# main-single-esp32.net
KiCad netlist of a schematic drawn in EAGLE
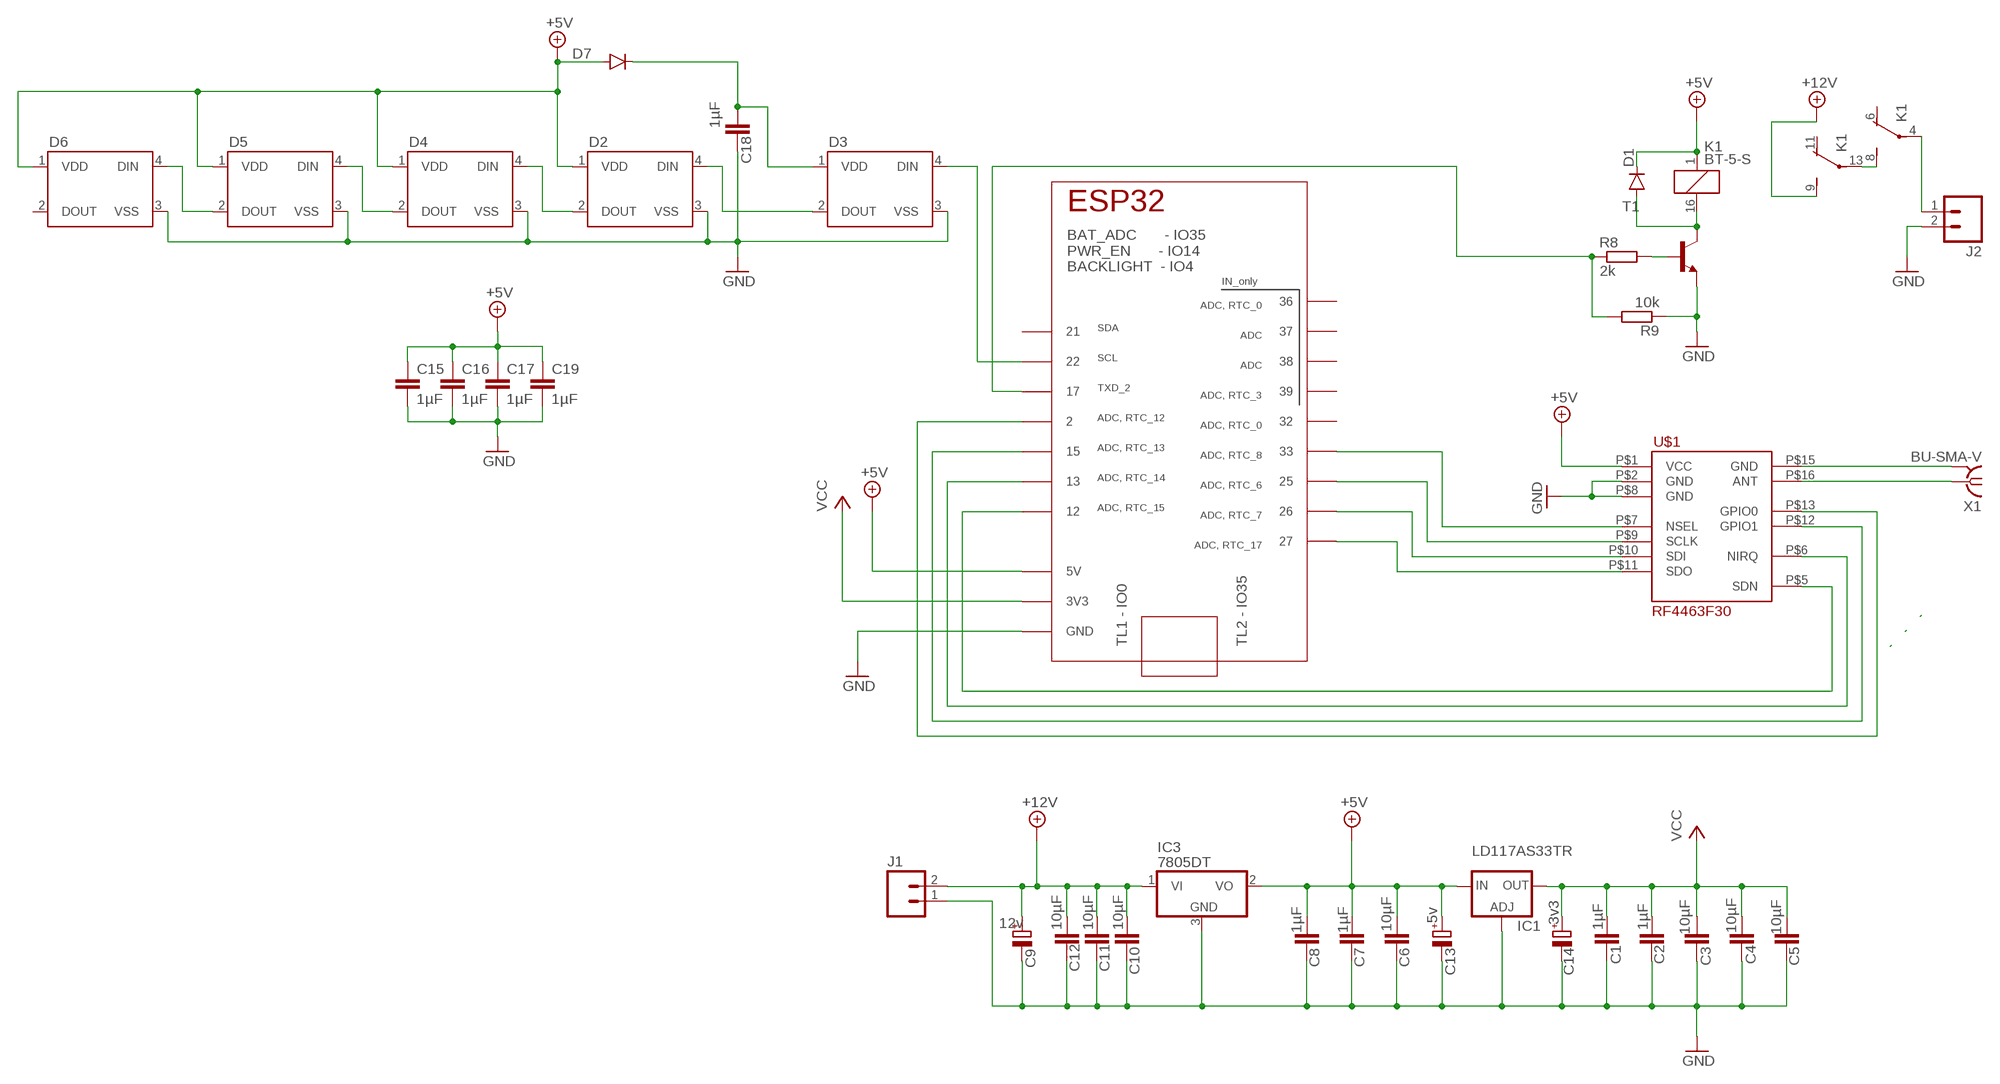
[diagram p0: schematic, sheet 1]

(export (version "E")
  (design (tool "Eeschema 10.0.6"))
  (components
    (comp (ref "C1")
      (value "1µF")
      (footprint "eagle-import:C1206K")
      (libsource (lib "eagle-import") (part "C-EUC1206K"))
    )
    (comp (ref "C2")
      (value "1µF")
      (footprint "eagle-import:C1206K")
      (libsource (lib "eagle-import") (part "C-EUC1206K"))
    )
    (comp (ref "C3")
      (value "10µF")
      (footprint "eagle-import:C1206K")
      (libsource (lib "eagle-import") (part "C-EUC1206K"))
    )
    (comp (ref "C4")
      (value "10µF")
      (footprint "eagle-import:C1206K")
      (libsource (lib "eagle-import") (part "C-EUC1206K"))
    )
    (comp (ref "C5")
      (value "10µF")
      (footprint "eagle-import:C1206K")
      (libsource (lib "eagle-import") (part "C-EUC1206K"))
    )
    (comp (ref "C6")
      (value "10µF")
      (footprint "eagle-import:C1206K")
      (libsource (lib "eagle-import") (part "C-EUC1206K"))
    )
    (comp (ref "C7")
      (value "1µF")
      (footprint "eagle-import:C1206K")
      (libsource (lib "eagle-import") (part "C-EUC1206K"))
    )
    (comp (ref "C8")
      (value "1µF")
      (footprint "eagle-import:C1206K")
      (libsource (lib "eagle-import") (part "C-EUC1206K"))
    )
    (comp (ref "C9")
      (value "12v")
      (footprint "eagle-import:D_7343-31W")
      (libsource (lib "eagle-import") (part "CPOL-EUD/7343-31W"))
    )
    (comp (ref "C10")
      (value "10µF")
      (footprint "eagle-import:C1206K")
      (libsource (lib "eagle-import") (part "C-EUC1206K"))
    )
    (comp (ref "C11")
      (value "10µF")
      (footprint "eagle-import:C1206K")
      (libsource (lib "eagle-import") (part "C-EUC1206K"))
    )
    (comp (ref "C12")
      (value "10µF")
      (footprint "eagle-import:C1206K")
      (libsource (lib "eagle-import") (part "C-EUC1206K"))
    )
    (comp (ref "C13")
      (value "5v")
      (footprint "eagle-import:D_7343-31W")
      (libsource (lib "eagle-import") (part "CPOL-EUD/7343-31W"))
    )
    (comp (ref "C14")
      (value "3v3")
      (footprint "eagle-import:D_7343-31W")
      (libsource (lib "eagle-import") (part "CPOL-EUD/7343-31W"))
    )
    (comp (ref "C15")
      (value "1µF")
      (footprint "eagle-import:C0805")
      (libsource (lib "eagle-import") (part "C-EUC0805"))
    )
    (comp (ref "C16")
      (value "1µF")
      (footprint "eagle-import:C0805")
      (libsource (lib "eagle-import") (part "C-EUC0805"))
    )
    (comp (ref "C17")
      (value "1µF")
      (footprint "eagle-import:C0805")
      (libsource (lib "eagle-import") (part "C-EUC0805"))
    )
    (comp (ref "C18")
      (value "1µF")
      (footprint "eagle-import:C0805")
      (libsource (lib "eagle-import") (part "C-EUC0805"))
    )
    (comp (ref "C19")
      (value "1µF")
      (footprint "eagle-import:C0805")
      (libsource (lib "eagle-import") (part "C-EUC0805"))
    )
    (comp (ref "D1")
      (value "DIODESMA")
      (footprint "eagle-import:SMA-DIODE")
      (libsource (lib "eagle-import") (part "DIODESMA"))
    )
    (comp (ref "D2")
      (value "WS2812B")
      (footprint "eagle-import:WS2812B")
      (libsource (lib "eagle-import") (part "WS2812B"))
    )
    (comp (ref "D3")
      (value "WS2812B")
      (footprint "eagle-import:WS2812B")
      (libsource (lib "eagle-import") (part "WS2812B"))
    )
    (comp (ref "D4")
      (value "WS2812B")
      (footprint "eagle-import:WS2812B")
      (libsource (lib "eagle-import") (part "WS2812B"))
    )
    (comp (ref "D5")
      (value "WS2812B")
      (footprint "eagle-import:WS2812B")
      (libsource (lib "eagle-import") (part "WS2812B"))
    )
    (comp (ref "D6")
      (value "WS2812B")
      (footprint "eagle-import:WS2812B")
      (libsource (lib "eagle-import") (part "WS2812B"))
    )
    (comp (ref "D7")
      (value "DIODESMA")
      (footprint "eagle-import:SMA-DIODE")
      (libsource (lib "eagle-import") (part "DIODESMA"))
    )
    (comp (ref "IC1")
      (value "LD117AS33TR")
      (footprint "eagle-import:SOT223")
      (libsource (lib "eagle-import") (part "LD117A?S33TR"))
    )
    (comp (ref "IC2")
      (value "TTGO_DISP")
      (footprint "eagle-import:TTGO_DISP_DEFAULT")
      (libsource (lib "eagle-import") (part "TTGO_DISP"))
    )
    (comp (ref "IC3")
      (value "7805DT")
      (footprint "eagle-import:TO252")
      (libsource (lib "eagle-import") (part "78DT05"))
    )
    (comp (ref "J1")
      (value "M023.5MM-NO_SILK")
      (footprint "eagle-import:SCREWTERMINAL-3.5MM-2-NS")
      (libsource (lib "eagle-import") (part "M023.5MM-NO_SILK"))
    )
    (comp (ref "J2")
      (value "M023.5MM-NO_SILK")
      (footprint "eagle-import:SCREWTERMINAL-3.5MM-2-NS")
      (libsource (lib "eagle-import") (part "M023.5MM-NO_SILK"))
    )
    (comp (ref "K1")
      (value "BT-5-S")
      (footprint "eagle-import:BT-XX-S")
      (libsource (lib "eagle-import") (part "BT--S5"))
    )
    (comp (ref "R8")
      (value "2k")
      (footprint "eagle-import:R1206")
      (libsource (lib "eagle-import") (part "R-EU_R1206"))
    )
    (comp (ref "R9")
      (value "10k")
      (footprint "eagle-import:R1206")
      (libsource (lib "eagle-import") (part "R-EU_R1206"))
    )
    (comp (ref "T1")
      (value "MMBT2222ALT1-NPN-SOT23-BEC")
      (footprint "eagle-import:SOT23-BEC")
      (libsource (lib "eagle-import") (part "-NPN-SOT23-BECMMBT2222ALT1"))
    )
    (comp (ref "U$1")
      (value "RF4463F30")
      (footprint "eagle-import:NICERF_16PIN_SPI_TRANSCEIVER")
      (libsource (lib "eagle-import") (part "RF4463F30"))
    )
    (comp (ref "X1")
      (value "BU-SMA-V")
      (footprint "eagle-import:BU-SMA-V")
      (libsource (lib "eagle-import") (part "BU-SMA-V"))
    )
  )
  (nets
    (net (code "1") (name "+5V") (class "Default")
      (node (ref "C13") (pin "+") (pinfunction "+_+") (pintype "passive"))
      (node (ref "C15") (pin "1") (pinfunction "1_1") (pintype "passive"))
      (node (ref "C16") (pin "1") (pinfunction "1_1") (pintype "passive"))
      (node (ref "C17") (pin "1") (pinfunction "1_1") (pintype "passive"))
      (node (ref "C19") (pin "1") (pinfunction "1_1") (pintype "passive"))
      (node (ref "C6") (pin "1") (pinfunction "1_1") (pintype "passive"))
      (node (ref "C7") (pin "1") (pinfunction "1_1") (pintype "passive"))
      (node (ref "C8") (pin "1") (pinfunction "1_1") (pintype "passive"))
      (node (ref "D1") (pin "C") (pinfunction "C_C") (pintype "passive"))
      (node (ref "D2") (pin "1") (pinfunction "VDD_1") (pintype "power_in"))
      (node (ref "D4") (pin "1") (pinfunction "VDD_1") (pintype "power_in"))
      (node (ref "D5") (pin "1") (pinfunction "VDD_1") (pintype "power_in"))
      (node (ref "D6") (pin "1") (pinfunction "VDD_1") (pintype "power_in"))
      (node (ref "D7") (pin "A") (pinfunction "A_A") (pintype "passive"))
      (node (ref "IC1") (pin "3") (pinfunction "IN_3") (pintype "input"))
      (node (ref "IC2") (pin "5V") (pinfunction "5V_5V") (pintype "bidirectional"))
      (node (ref "IC3") (pin "2") (pinfunction "VO_2") (pintype "passive"))
      (node (ref "K1") (pin "1") (pinfunction "1_1") (pintype "passive"))
      (node (ref "U$1") (pin "P$1") (pinfunction "VCC_P$1") (pintype "bidirectional"))
    )
    (net (code "2") (name "+12V") (class "Default")
      (node (ref "C10") (pin "1") (pinfunction "1_1") (pintype "passive"))
      (node (ref "C11") (pin "1") (pinfunction "1_1") (pintype "passive"))
      (node (ref "C12") (pin "1") (pinfunction "1_1") (pintype "passive"))
      (node (ref "C9") (pin "+") (pinfunction "+_+") (pintype "passive"))
      (node (ref "IC3") (pin "1") (pinfunction "VI_1") (pintype "input"))
      (node (ref "J1") (pin "2") (pinfunction "2_2") (pintype "passive"))
      (node (ref "K1") (pin "9") (pinfunction "S_9") (pintype "passive"))
    )
    (net (code "3") (name "GND") (class "Default")
      (node (ref "C1") (pin "2") (pinfunction "2_2") (pintype "passive"))
      (node (ref "C10") (pin "2") (pinfunction "2_2") (pintype "passive"))
      (node (ref "C11") (pin "2") (pinfunction "2_2") (pintype "passive"))
      (node (ref "C12") (pin "2") (pinfunction "2_2") (pintype "passive"))
      (node (ref "C13") (pin "-") (pinfunction "-_-") (pintype "passive"))
      (node (ref "C14") (pin "-") (pinfunction "-_-") (pintype "passive"))
      (node (ref "C15") (pin "2") (pinfunction "2_2") (pintype "passive"))
      (node (ref "C16") (pin "2") (pinfunction "2_2") (pintype "passive"))
      (node (ref "C17") (pin "2") (pinfunction "2_2") (pintype "passive"))
      (node (ref "C18") (pin "2") (pinfunction "2_2") (pintype "passive"))
      (node (ref "C19") (pin "2") (pinfunction "2_2") (pintype "passive"))
      (node (ref "C2") (pin "2") (pinfunction "2_2") (pintype "passive"))
      (node (ref "C3") (pin "2") (pinfunction "2_2") (pintype "passive"))
      (node (ref "C4") (pin "2") (pinfunction "2_2") (pintype "passive"))
      (node (ref "C5") (pin "2") (pinfunction "2_2") (pintype "passive"))
      (node (ref "C6") (pin "2") (pinfunction "2_2") (pintype "passive"))
      (node (ref "C7") (pin "2") (pinfunction "2_2") (pintype "passive"))
      (node (ref "C8") (pin "2") (pinfunction "2_2") (pintype "passive"))
      (node (ref "C9") (pin "-") (pinfunction "-_-") (pintype "passive"))
      (node (ref "D2") (pin "3") (pinfunction "VSS_3") (pintype "power_in"))
      (node (ref "D3") (pin "3") (pinfunction "VSS_3") (pintype "power_in"))
      (node (ref "D4") (pin "3") (pinfunction "VSS_3") (pintype "power_in"))
      (node (ref "D5") (pin "3") (pinfunction "VSS_3") (pintype "power_in"))
      (node (ref "D6") (pin "3") (pinfunction "VSS_3") (pintype "power_in"))
      (node (ref "IC1") (pin "1") (pinfunction "ADJ_1") (pintype "input"))
      (node (ref "IC2") (pin "GND_1") (pinfunction "GND_GND_1") (pintype "bidirectional"))
      (node (ref "IC2") (pin "GND_2") (pinfunction "GND_GND_2") (pintype "bidirectional"))
      (node (ref "IC2") (pin "GND_3") (pinfunction "GND_GND_3") (pintype "bidirectional"))
      (node (ref "IC2") (pin "GND_4") (pinfunction "GND_GND_4") (pintype "bidirectional"))
      (node (ref "IC2") (pin "GND_5") (pinfunction "GND_GND_5") (pintype "bidirectional"))
      (node (ref "IC3") (pin "3") (pinfunction "GND_3") (pintype "passive"))
      (node (ref "J1") (pin "1") (pinfunction "1_1") (pintype "passive"))
      (node (ref "J2") (pin "2") (pinfunction "2_2") (pintype "passive"))
      (node (ref "R9") (pin "1") (pinfunction "1_1") (pintype "passive"))
      (node (ref "T1") (pin "E") (pinfunction "E_E") (pintype "passive"))
      (node (ref "U$1") (pin "P$2") (pinfunction "GND_P$2") (pintype "bidirectional"))
      (node (ref "U$1") (pin "P$8") (pinfunction "GND_P$8") (pintype "bidirectional"))
    )
    (net (code "4") (name "Net-(D2-DIN)") (class "Default")
      (node (ref "D2") (pin "4") (pinfunction "DIN_4") (pintype "input"))
      (node (ref "D3") (pin "2") (pinfunction "DOUT_2") (pintype "output"))
    )
    (net (code "5") (name "Net-(D2-DOUT)") (class "Default")
      (node (ref "D2") (pin "2") (pinfunction "DOUT_2") (pintype "output"))
      (node (ref "D4") (pin "4") (pinfunction "DIN_4") (pintype "input"))
    )
    (net (code "6") (name "Net-(D3-DIN)") (class "Default")
      (node (ref "D3") (pin "4") (pinfunction "DIN_4") (pintype "input"))
      (node (ref "IC2") (pin "22") (pinfunction "22_22") (pintype "bidirectional"))
    )
    (net (code "7") (name "Net-(D3-VDD)") (class "Default")
      (node (ref "C18") (pin "1") (pinfunction "1_1") (pintype "passive"))
      (node (ref "D3") (pin "1") (pinfunction "VDD_1") (pintype "power_in"))
      (node (ref "D7") (pin "C") (pinfunction "C_C") (pintype "passive"))
    )
    (net (code "8") (name "Net-(D4-DOUT)") (class "Default")
      (node (ref "D4") (pin "2") (pinfunction "DOUT_2") (pintype "output"))
      (node (ref "D5") (pin "4") (pinfunction "DIN_4") (pintype "input"))
    )
    (net (code "9") (name "Net-(D5-DOUT)") (class "Default")
      (node (ref "D5") (pin "2") (pinfunction "DOUT_2") (pintype "output"))
      (node (ref "D6") (pin "4") (pinfunction "DIN_4") (pintype "input"))
    )
    (net (code "10") (name "Net-(IC2-Pad17)") (class "Default")
      (node (ref "IC2") (pin "17") (pinfunction "17_17") (pintype "bidirectional"))
      (node (ref "R8") (pin "1") (pinfunction "1_1") (pintype "passive"))
      (node (ref "R9") (pin "2") (pinfunction "2_2") (pintype "passive"))
    )
    (net (code "11") (name "Net-(K1A-P)") (class "Default")
      (node (ref "J2") (pin "1") (pinfunction "1_1") (pintype "passive"))
      (node (ref "K1") (pin "4") (pinfunction "P_4") (pintype "passive"))
    )
    (net (code "12") (name "Net-(K1A-S)") (class "Default")
      (node (ref "K1") (pin "13") (pinfunction "P_13") (pintype "passive"))
      (node (ref "K1") (pin "8") (pinfunction "S_8") (pintype "passive"))
    )
    (net (code "13") (name "Net-(K1C-2)") (class "Default")
      (node (ref "D1") (pin "A") (pinfunction "A_A") (pintype "passive"))
      (node (ref "K1") (pin "16") (pinfunction "2_16") (pintype "passive"))
      (node (ref "T1") (pin "C") (pinfunction "C_C") (pintype "passive"))
    )
    (net (code "14") (name "Net-(R8-Pad2)") (class "Default")
      (node (ref "R8") (pin "2") (pinfunction "2_2") (pintype "passive"))
      (node (ref "T1") (pin "B") (pinfunction "B_B") (pintype "passive"))
    )
    (net (code "15") (name "Net-(U$1-ANT)") (class "Default")
      (node (ref "U$1") (pin "P$16") (pinfunction "ANT_P$16") (pintype "bidirectional"))
      (node (ref "X1") (pin "1") (pinfunction "1_1") (pintype "passive"))
    )
    (net (code "16") (name "Net-(U$1-GND-PadP$15)") (class "Default")
      (node (ref "U$1") (pin "P$15") (pinfunction "GND_P$15") (pintype "bidirectional"))
      (node (ref "X1") (pin "2") (pinfunction "2_2") (pintype "passive"))
      (node (ref "X1") (pin "3") (pinfunction "2_3") (pintype "passive"))
      (node (ref "X1") (pin "4") (pinfunction "2_4") (pintype "passive"))
      (node (ref "X1") (pin "5") (pinfunction "2_5") (pintype "passive"))
    )
    (net (code "17") (name "Net-(U$1-GPIO0)") (class "Default")
      (node (ref "IC2") (pin "2") (pinfunction "2_2") (pintype "bidirectional"))
      (node (ref "U$1") (pin "P$13") (pinfunction "GPIO0_P$13") (pintype "bidirectional"))
    )
    (net (code "18") (name "Net-(U$1-GPIO1)") (class "Default")
      (node (ref "IC2") (pin "15") (pinfunction "15_15") (pintype "bidirectional"))
      (node (ref "U$1") (pin "P$12") (pinfunction "GPIO1_P$12") (pintype "bidirectional"))
    )
    (net (code "19") (name "Net-(U$1-NIRQ)") (class "Default")
      (node (ref "IC2") (pin "13") (pinfunction "13_13") (pintype "bidirectional"))
      (node (ref "U$1") (pin "P$6") (pinfunction "NIRQ_P$6") (pintype "bidirectional"))
    )
    (net (code "20") (name "Net-(U$1-NSEL)") (class "Default")
      (node (ref "IC2") (pin "33") (pinfunction "33_33") (pintype "bidirectional"))
      (node (ref "U$1") (pin "P$7") (pinfunction "NSEL_P$7") (pintype "bidirectional"))
    )
    (net (code "21") (name "Net-(U$1-SCLK)") (class "Default")
      (node (ref "IC2") (pin "25") (pinfunction "25_25") (pintype "bidirectional"))
      (node (ref "U$1") (pin "P$9") (pinfunction "SCLK_P$9") (pintype "bidirectional"))
    )
    (net (code "22") (name "Net-(U$1-SDI)") (class "Default")
      (node (ref "IC2") (pin "26") (pinfunction "26_26") (pintype "bidirectional"))
      (node (ref "U$1") (pin "P$10") (pinfunction "SDI_P$10") (pintype "bidirectional"))
    )
    (net (code "23") (name "Net-(U$1-SDN)") (class "Default")
      (node (ref "IC2") (pin "12") (pinfunction "12_12") (pintype "bidirectional"))
      (node (ref "U$1") (pin "P$5") (pinfunction "SDN_P$5") (pintype "bidirectional"))
    )
    (net (code "24") (name "Net-(U$1-SDO)") (class "Default")
      (node (ref "IC2") (pin "27") (pinfunction "27_27") (pintype "bidirectional"))
      (node (ref "U$1") (pin "P$11") (pinfunction "SDO_P$11") (pintype "bidirectional"))
    )
    (net (code "25") (name "VCC") (class "Default")
      (node (ref "C1") (pin "1") (pinfunction "1_1") (pintype "passive"))
      (node (ref "C14") (pin "+") (pinfunction "+_+") (pintype "passive"))
      (node (ref "C2") (pin "1") (pinfunction "1_1") (pintype "passive"))
      (node (ref "C3") (pin "1") (pinfunction "1_1") (pintype "passive"))
      (node (ref "C4") (pin "1") (pinfunction "1_1") (pintype "passive"))
      (node (ref "C5") (pin "1") (pinfunction "1_1") (pintype "passive"))
      (node (ref "IC1") (pin "4") (pinfunction "OUT_4") (pintype "passive"))
      (node (ref "IC2") (pin "3V3_1") (pinfunction "3V3_3V3_1") (pintype "bidirectional"))
      (node (ref "IC2") (pin "3V3_2") (pinfunction "3V3_3V3_2") (pintype "bidirectional"))
    )
    (net (code "26") (name "unconnected-(D6-DOUT-Pad2)") (class "Default")
      (node (ref "D6") (pin "2") (pinfunction "DOUT_2") (pintype "output"))
    )
    (net (code "27") (name "unconnected-(IC2-Pad21)") (class "Default")
      (node (ref "IC2") (pin "21") (pinfunction "21_21") (pintype "bidirectional"))
    )
    (net (code "28") (name "unconnected-(IC2-Pad32)") (class "Default")
      (node (ref "IC2") (pin "32") (pinfunction "32_32") (pintype "bidirectional"))
    )
    (net (code "29") (name "unconnected-(IC2-Pad36)") (class "Default")
      (node (ref "IC2") (pin "36") (pinfunction "36_36") (pintype "bidirectional"))
    )
    (net (code "30") (name "unconnected-(IC2-Pad37)") (class "Default")
      (node (ref "IC2") (pin "37") (pinfunction "37_37") (pintype "bidirectional"))
    )
    (net (code "31") (name "unconnected-(IC2-Pad38)") (class "Default")
      (node (ref "IC2") (pin "38") (pinfunction "38_38") (pintype "bidirectional"))
    )
    (net (code "32") (name "unconnected-(IC2-Pad39)") (class "Default")
      (node (ref "IC2") (pin "39") (pinfunction "39_39") (pintype "bidirectional"))
    )
    (net (code "33") (name "unconnected-(K1A-O-Pad6)") (class "Default")
      (node (ref "K1") (pin "6") (pinfunction "O_6") (pintype "passive"))
    )
    (net (code "34") (name "unconnected-(K1B-O-Pad11)") (class "Default")
      (node (ref "K1") (pin "11") (pinfunction "O_11") (pintype "passive"))
    )
  )
)
